# seg_v2.net
KiCad netlist of a schematic drawn in EAGLE
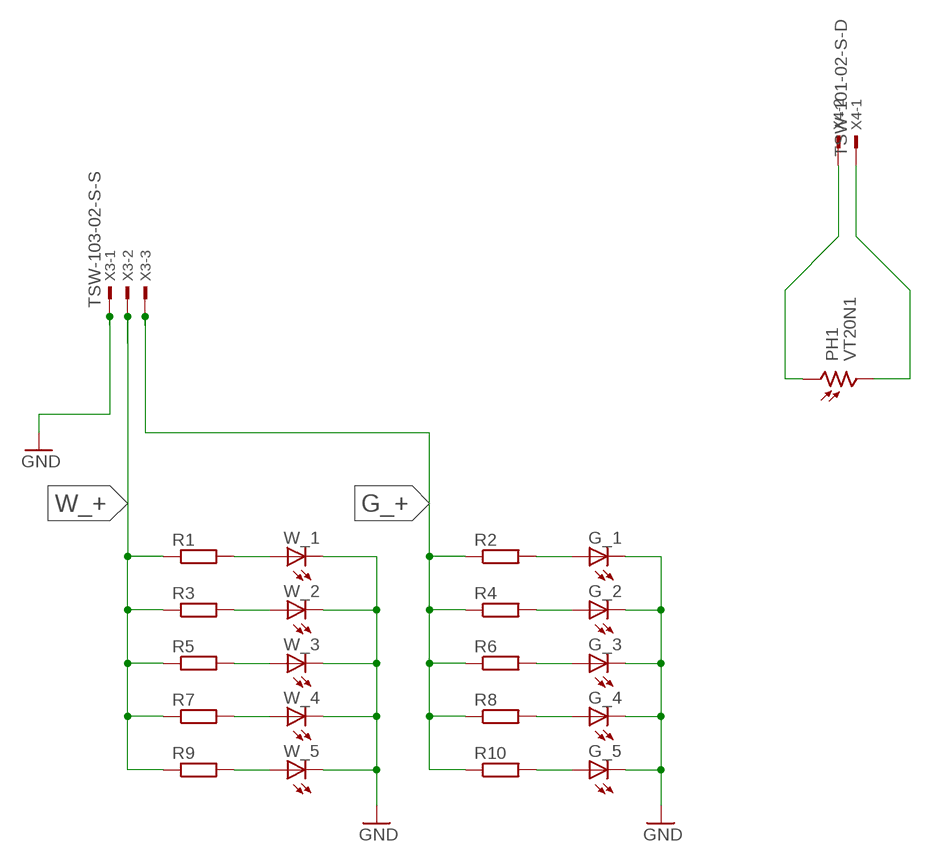
[diagram p0: schematic, sheet 1]

(export (version "E")
  (design (tool "Eeschema 10.0.6"))
  (components
    (comp (ref "G_1")
      (value "LEDSML0603")
      (footprint "eagle-import:SML0603")
      (libsource (lib "eagle-import") (part "LEDSML0603"))
    )
    (comp (ref "G_2")
      (value "LEDSML0603")
      (footprint "eagle-import:SML0603")
      (libsource (lib "eagle-import") (part "LEDSML0603"))
    )
    (comp (ref "G_3")
      (value "LEDSML0603")
      (footprint "eagle-import:SML0603")
      (libsource (lib "eagle-import") (part "LEDSML0603"))
    )
    (comp (ref "G_4")
      (value "LEDSML0603")
      (footprint "eagle-import:SML0603")
      (libsource (lib "eagle-import") (part "LEDSML0603"))
    )
    (comp (ref "G_5")
      (value "LEDSML0603")
      (footprint "eagle-import:SML0603")
      (libsource (lib "eagle-import") (part "LEDSML0603"))
    )
    (comp (ref "PH1")
      (value "VT20N1")
      (footprint "eagle-import:TO46-VT200")
      (libsource (lib "eagle-import") (part "VT20N1"))
    )
    (comp (ref "R1")
      (value "R-EU_R0603")
      (footprint "eagle-import:R0603")
      (libsource (lib "eagle-import") (part "R-EU_R0603"))
    )
    (comp (ref "R2")
      (value "R-EU_R0603")
      (footprint "eagle-import:R0603")
      (libsource (lib "eagle-import") (part "R-EU_R0603"))
    )
    (comp (ref "R3")
      (value "R-EU_R0603")
      (footprint "eagle-import:R0603")
      (libsource (lib "eagle-import") (part "R-EU_R0603"))
    )
    (comp (ref "R4")
      (value "R-EU_R0603")
      (footprint "eagle-import:R0603")
      (libsource (lib "eagle-import") (part "R-EU_R0603"))
    )
    (comp (ref "R5")
      (value "R-EU_R0603")
      (footprint "eagle-import:R0603")
      (libsource (lib "eagle-import") (part "R-EU_R0603"))
    )
    (comp (ref "R6")
      (value "R-EU_R0603")
      (footprint "eagle-import:R0603")
      (libsource (lib "eagle-import") (part "R-EU_R0603"))
    )
    (comp (ref "R7")
      (value "R-EU_R0603")
      (footprint "eagle-import:R0603")
      (libsource (lib "eagle-import") (part "R-EU_R0603"))
    )
    (comp (ref "R8")
      (value "R-EU_R0603")
      (footprint "eagle-import:R0603")
      (libsource (lib "eagle-import") (part "R-EU_R0603"))
    )
    (comp (ref "R9")
      (value "R-EU_R0603")
      (footprint "eagle-import:R0603")
      (libsource (lib "eagle-import") (part "R-EU_R0603"))
    )
    (comp (ref "R10")
      (value "R-EU_R0603")
      (footprint "eagle-import:R0603")
      (libsource (lib "eagle-import") (part "R-EU_R0603"))
    )
    (comp (ref "W_1")
      (value "LEDSML0603")
      (footprint "eagle-import:SML0603")
      (libsource (lib "eagle-import") (part "LEDSML0603"))
    )
    (comp (ref "W_2")
      (value "LEDSML0603")
      (footprint "eagle-import:SML0603")
      (libsource (lib "eagle-import") (part "LEDSML0603"))
    )
    (comp (ref "W_3")
      (value "LEDSML0603")
      (footprint "eagle-import:SML0603")
      (libsource (lib "eagle-import") (part "LEDSML0603"))
    )
    (comp (ref "W_4")
      (value "LEDSML0603")
      (footprint "eagle-import:SML0603")
      (libsource (lib "eagle-import") (part "LEDSML0603"))
    )
    (comp (ref "W_5")
      (value "LEDSML0603")
      (footprint "eagle-import:SML0603")
      (libsource (lib "eagle-import") (part "LEDSML0603"))
    )
    (comp (ref "X3")
      (value "TSW-103-02-S-S")
      (footprint "eagle-import:TSW-103-02-S-S")
      (libsource (lib "eagle-import") (part "TSW-103-02-S-S"))
    )
    (comp (ref "X4")
      (value "TSW-101-02-S-D")
      (footprint "eagle-import:TSW-101-02-S-D")
      (libsource (lib "eagle-import") (part "TSW-101-02-S-D"))
    )
  )
  (nets
    (net (code "1") (name "GND") (class "Default")
      (node (ref "G_1") (pin "C") (pinfunction "C_C") (pintype "passive"))
      (node (ref "G_2") (pin "C") (pinfunction "C_C") (pintype "passive"))
      (node (ref "G_3") (pin "C") (pinfunction "C_C") (pintype "passive"))
      (node (ref "G_4") (pin "C") (pinfunction "C_C") (pintype "passive"))
      (node (ref "G_5") (pin "C") (pinfunction "C_C") (pintype "passive"))
      (node (ref "W_1") (pin "C") (pinfunction "C_C") (pintype "passive"))
      (node (ref "W_2") (pin "C") (pinfunction "C_C") (pintype "passive"))
      (node (ref "W_3") (pin "C") (pinfunction "C_C") (pintype "passive"))
      (node (ref "W_4") (pin "C") (pinfunction "C_C") (pintype "passive"))
      (node (ref "W_5") (pin "C") (pinfunction "C_C") (pintype "passive"))
      (node (ref "X3") (pin "1") (pinfunction "1_1") (pintype "passive"))
    )
    (net (code "2") (name "G_+") (class "Default")
      (node (ref "R10") (pin "1") (pinfunction "1_1") (pintype "passive"))
      (node (ref "R2") (pin "1") (pinfunction "1_1") (pintype "passive"))
      (node (ref "R4") (pin "1") (pinfunction "1_1") (pintype "passive"))
      (node (ref "R6") (pin "1") (pinfunction "1_1") (pintype "passive"))
      (node (ref "R8") (pin "1") (pinfunction "1_1") (pintype "passive"))
      (node (ref "X3") (pin "3") (pinfunction "1_3") (pintype "passive"))
    )
    (net (code "3") (name "Net-(G_1-PadA)") (class "Default")
      (node (ref "G_1") (pin "A") (pinfunction "A_A") (pintype "passive"))
      (node (ref "R2") (pin "2") (pinfunction "2_2") (pintype "passive"))
    )
    (net (code "4") (name "Net-(G_2-PadA)") (class "Default")
      (node (ref "G_2") (pin "A") (pinfunction "A_A") (pintype "passive"))
      (node (ref "R4") (pin "2") (pinfunction "2_2") (pintype "passive"))
    )
    (net (code "5") (name "Net-(G_3-PadA)") (class "Default")
      (node (ref "G_3") (pin "A") (pinfunction "A_A") (pintype "passive"))
      (node (ref "R6") (pin "2") (pinfunction "2_2") (pintype "passive"))
    )
    (net (code "6") (name "Net-(G_4-PadA)") (class "Default")
      (node (ref "G_4") (pin "A") (pinfunction "A_A") (pintype "passive"))
      (node (ref "R8") (pin "2") (pinfunction "2_2") (pintype "passive"))
    )
    (net (code "7") (name "Net-(G_5-PadA)") (class "Default")
      (node (ref "G_5") (pin "A") (pinfunction "A_A") (pintype "passive"))
      (node (ref "R10") (pin "2") (pinfunction "2_2") (pintype "passive"))
    )
    (net (code "8") (name "Net-(PH1-Pad2)") (class "Default")
      (node (ref "PH1") (pin "2") (pinfunction "2_2") (pintype "passive"))
      (node (ref "X4") (pin "1") (pinfunction "1_1") (pintype "passive"))
    )
    (net (code "9") (name "Net-(R1-Pad2)") (class "Default")
      (node (ref "R1") (pin "2") (pinfunction "2_2") (pintype "passive"))
      (node (ref "W_1") (pin "A") (pinfunction "A_A") (pintype "passive"))
    )
    (net (code "10") (name "Net-(R3-Pad2)") (class "Default")
      (node (ref "R3") (pin "2") (pinfunction "2_2") (pintype "passive"))
      (node (ref "W_2") (pin "A") (pinfunction "A_A") (pintype "passive"))
    )
    (net (code "11") (name "Net-(R5-Pad2)") (class "Default")
      (node (ref "R5") (pin "2") (pinfunction "2_2") (pintype "passive"))
      (node (ref "W_3") (pin "A") (pinfunction "A_A") (pintype "passive"))
    )
    (net (code "12") (name "Net-(R7-Pad2)") (class "Default")
      (node (ref "R7") (pin "2") (pinfunction "2_2") (pintype "passive"))
      (node (ref "W_4") (pin "A") (pinfunction "A_A") (pintype "passive"))
    )
    (net (code "13") (name "Net-(R9-Pad2)") (class "Default")
      (node (ref "R9") (pin "2") (pinfunction "2_2") (pintype "passive"))
      (node (ref "W_5") (pin "A") (pinfunction "A_A") (pintype "passive"))
    )
    (net (code "14") (name "Net-(X4B-1)") (class "Default")
      (node (ref "PH1") (pin "1") (pinfunction "1_1") (pintype "passive"))
      (node (ref "X4") (pin "2") (pinfunction "1_2") (pintype "passive"))
    )
    (net (code "15") (name "W_+") (class "Default")
      (node (ref "R1") (pin "1") (pinfunction "1_1") (pintype "passive"))
      (node (ref "R3") (pin "1") (pinfunction "1_1") (pintype "passive"))
      (node (ref "R5") (pin "1") (pinfunction "1_1") (pintype "passive"))
      (node (ref "R7") (pin "1") (pinfunction "1_1") (pintype "passive"))
      (node (ref "R9") (pin "1") (pinfunction "1_1") (pintype "passive"))
      (node (ref "X3") (pin "2") (pinfunction "1_2") (pintype "passive"))
    )
  )
)
